# ESP32Board_Type-C.net
KiCad netlist of a schematic drawn in EAGLE
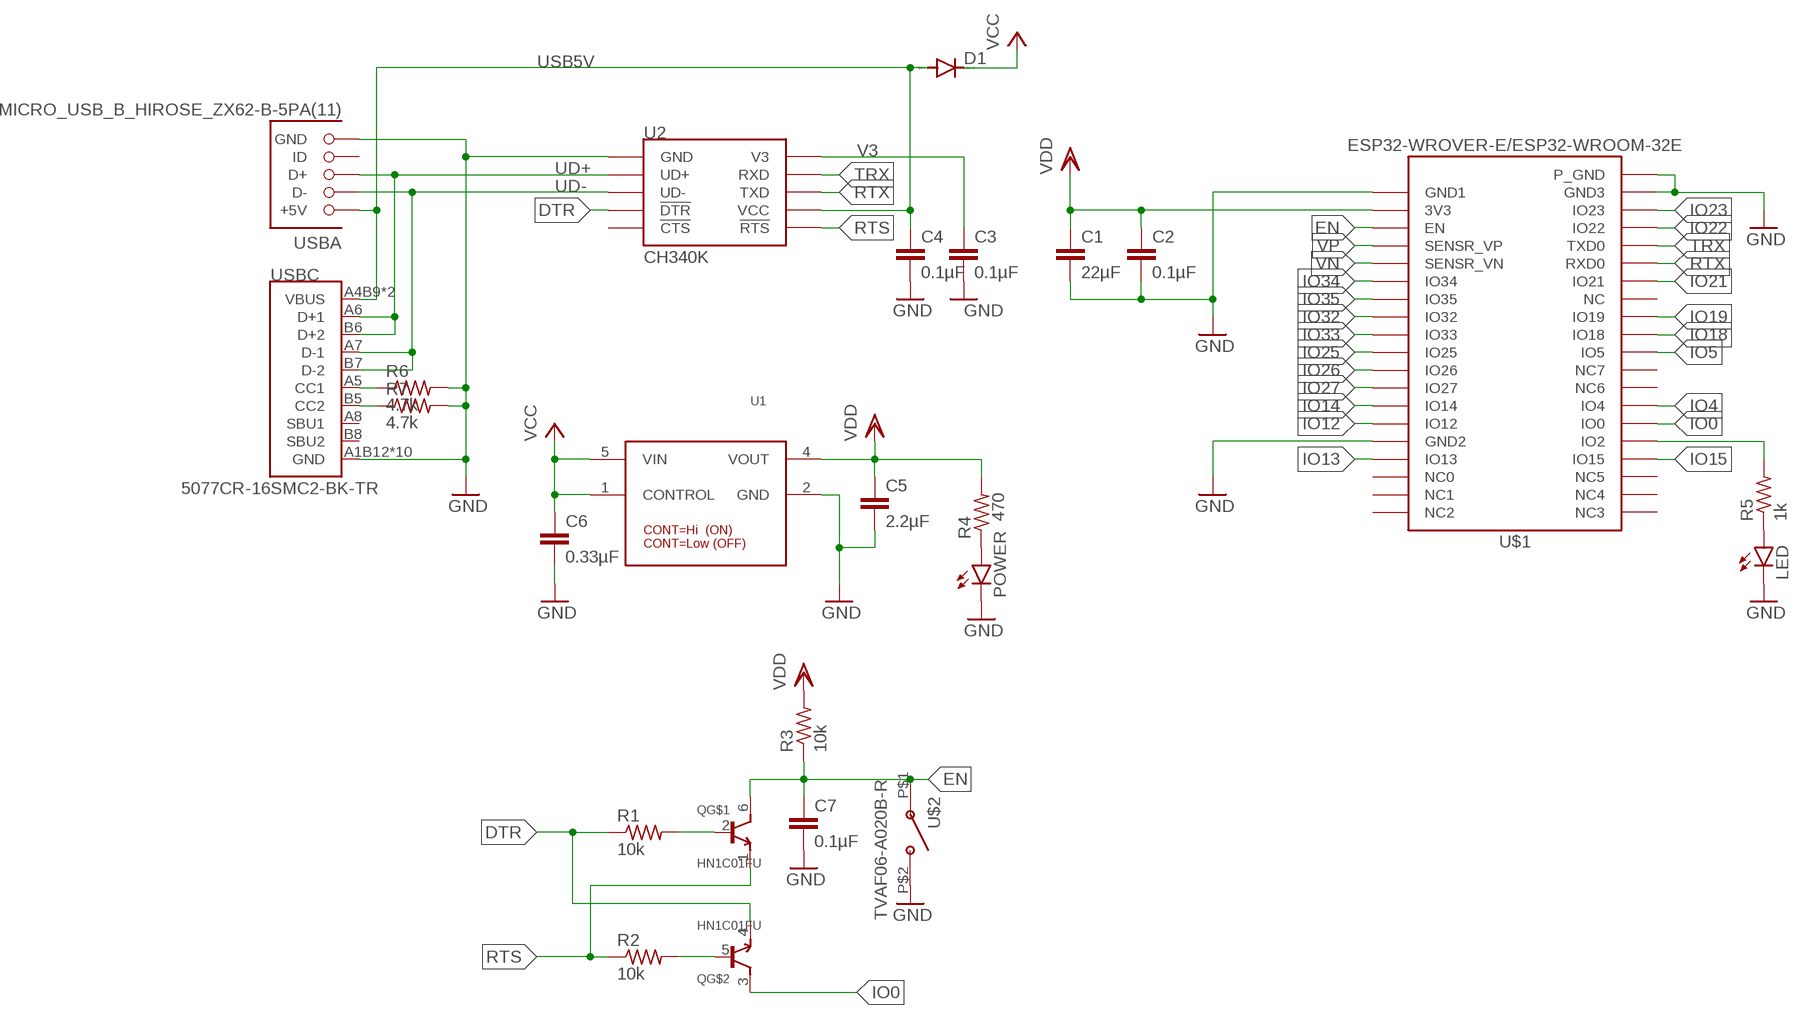
[diagram p0: schematic, sheet 1]

(export (version "E")
  (design (tool "Eeschema 10.0.6"))
  (components
    (comp (ref "C1")
      (value "22µF")
      (footprint "eagle-import:C0603K")
      (libsource (lib "eagle-import") (part "C-EUC0603K"))
    )
    (comp (ref "C2")
      (value "0.1µF")
      (footprint "eagle-import:C0603K")
      (libsource (lib "eagle-import") (part "C-EUC0603K"))
    )
    (comp (ref "C3")
      (value "0.1µF")
      (footprint "eagle-import:C0603K")
      (libsource (lib "eagle-import") (part "C-EUC0603K"))
    )
    (comp (ref "C4")
      (value "0.1µF")
      (footprint "eagle-import:C0603K")
      (libsource (lib "eagle-import") (part "C-EUC0603K"))
    )
    (comp (ref "C5")
      (value "2.2µF")
      (footprint "eagle-import:C0603K")
      (libsource (lib "eagle-import") (part "C-EUC0603K"))
    )
    (comp (ref "C6")
      (value "0.33µF")
      (footprint "eagle-import:C0603K")
      (libsource (lib "eagle-import") (part "C-EUC0603K"))
    )
    (comp (ref "C7")
      (value "0.1µF")
      (footprint "eagle-import:C0603K")
      (libsource (lib "eagle-import") (part "C-EUC0603K"))
    )
    (comp (ref "D1")
      (value "DIODE-SOD123")
      (footprint "eagle-import:SOD123")
      (libsource (lib "eagle-import") (part "DIODE-SOD123"))
    )
    (comp (ref "LED")
      (value "LEDCHIPLED_0603")
      (footprint "eagle-import:CHIPLED_0603")
      (libsource (lib "eagle-import") (part "LEDCHIPLED_0603"))
    )
    (comp (ref "POWER")
      (value "LEDCHIPLED_0603")
      (footprint "eagle-import:CHIPLED_0603")
      (libsource (lib "eagle-import") (part "LEDCHIPLED_0603"))
    )
    (comp (ref "Q")
      (value "HN1C01FU")
      (footprint "eagle-import:SOT-363")
      (libsource (lib "eagle-import") (part "HN1C01FU"))
    )
    (comp (ref "R1")
      (value "10k")
      (footprint "eagle-import:R0603")
      (libsource (lib "eagle-import") (part "R-US_R0603"))
    )
    (comp (ref "R2")
      (value "10k")
      (footprint "eagle-import:R0603")
      (libsource (lib "eagle-import") (part "R-US_R0603"))
    )
    (comp (ref "R3")
      (value "10k")
      (footprint "eagle-import:R0603")
      (libsource (lib "eagle-import") (part "R-US_R0603"))
    )
    (comp (ref "R4")
      (value "470")
      (footprint "eagle-import:R0603")
      (libsource (lib "eagle-import") (part "R-US_R0603"))
    )
    (comp (ref "R5")
      (value "1k")
      (footprint "eagle-import:R0603")
      (libsource (lib "eagle-import") (part "R-US_R0603"))
    )
    (comp (ref "R6")
      (value "4.7k")
      (footprint "eagle-import:R0603")
      (libsource (lib "eagle-import") (part "R-US_R0603"))
    )
    (comp (ref "R7")
      (value "4.7k")
      (footprint "eagle-import:R0603")
      (libsource (lib "eagle-import") (part "R-US_R0603"))
    )
    (comp (ref "U$1")
      (value "ESP32-WROVER-E/ESP32-WROOM-32E")
      (footprint "eagle-import:ESP32-WROVER-E_ESP32-WROOM-32E")
      (libsource (lib "eagle-import") (part "ESP32-WROVER-E/ESP32-WROOM-32E"))
    )
    (comp (ref "U$2")
      (value "TVAF06-A020B-R")
      (footprint "eagle-import:TVAF06-A020B-R")
      (libsource (lib "eagle-import") (part "TVAF06-A020B-R"))
    )
    (comp (ref "U1")
      (value "I-10673_NJM2884U1-33")
      (footprint "eagle-import:NJM2884U1-33")
      (libsource (lib "eagle-import") (part "I-10673_NJM2884U1-33"))
    )
    (comp (ref "U2")
      (value "CH340K")
      (footprint "eagle-import:ESSOP-10")
      (libsource (lib "eagle-import") (part "CH340K"))
    )
    (comp (ref "USBA")
      (value "MICRO_USB_B_HIROSE_ZX62-B-5PA(11)")
      (footprint "eagle-import:USB_MICRO_B-HIROSE-ZX62-B-5PA(11)")
      (libsource (lib "eagle-import") (part "MICRO_USB_B_HIROSE_ZX62-B-5PA(11)"))
    )
    (comp (ref "USBC")
      (value "5077CR-16SMC2-BK-TR")
      (footprint "eagle-import:5077CR-16SMC2-BK-TR")
      (libsource (lib "eagle-import") (part "5077CR-16SMC2-BK-TR"))
    )
  )
  (nets
    (net (code "1") (name "/UD+") (class "Default")
      (node (ref "U2") (pin "P1") (pinfunction "UD+_P1") (pintype "bidirectional"))
      (node (ref "USBA") (pin "3") (pinfunction "D+_3") (pintype "bidirectional"))
      (node (ref "USBC") (pin "A6") (pinfunction "D+1_A6") (pintype "bidirectional"))
      (node (ref "USBC") (pin "B6") (pinfunction "D+2_B6") (pintype "bidirectional"))
    )
    (net (code "2") (name "/UD-") (class "Default")
      (node (ref "U2") (pin "P2") (pinfunction "UD-_P2") (pintype "bidirectional"))
      (node (ref "USBA") (pin "2") (pinfunction "D-_2") (pintype "bidirectional"))
      (node (ref "USBC") (pin "A7") (pinfunction "D-1_A7") (pintype "bidirectional"))
      (node (ref "USBC") (pin "B7") (pinfunction "D-2_B7") (pintype "bidirectional"))
    )
    (net (code "3") (name "/USB5V") (class "Default")
      (node (ref "C4") (pin "1") (pinfunction "1_1") (pintype "passive"))
      (node (ref "D1") (pin "A") (pinfunction "A_A") (pintype "passive"))
      (node (ref "U2") (pin "P7") (pinfunction "VCC_P7") (pintype "power_in"))
      (node (ref "USBA") (pin "1") (pinfunction "+5V_1") (pintype "bidirectional"))
      (node (ref "USBC") (pin "A4B9") (pinfunction "VBUS_A4B9") (pintype "power_in"))
      (node (ref "USBC") (pin "B4A9") (pinfunction "VBUS_B4A9") (pintype "power_in"))
    )
    (net (code "4") (name "/V3") (class "Default")
      (node (ref "C3") (pin "1") (pinfunction "1_1") (pintype "passive"))
      (node (ref "U2") (pin "P10") (pinfunction "V3_P10") (pintype "power_in"))
    )
    (net (code "5") (name "DTR") (class "Default")
      (node (ref "Q") (pin "4") (pinfunction "E_4") (pintype "bidirectional"))
      (node (ref "R1") (pin "1") (pinfunction "1_1") (pintype "passive"))
      (node (ref "U2") (pin "P4") (pinfunction "~{DTR}_P4") (pintype "bidirectional"))
    )
    (net (code "6") (name "EN") (class "Default")
      (node (ref "C7") (pin "1") (pinfunction "1_1") (pintype "passive"))
      (node (ref "Q") (pin "6") (pinfunction "C_6") (pintype "bidirectional"))
      (node (ref "R3") (pin "1") (pinfunction "1_1") (pintype "passive"))
      (node (ref "U$1") (pin "EN") (pinfunction "EN_EN") (pintype "bidirectional"))
      (node (ref "U$2") (pin "P$1") (pinfunction "A_P$1") (pintype "bidirectional"))
    )
    (net (code "7") (name "GND") (class "Default")
      (node (ref "C1") (pin "2") (pinfunction "2_2") (pintype "passive"))
      (node (ref "C2") (pin "2") (pinfunction "2_2") (pintype "passive"))
      (node (ref "C3") (pin "2") (pinfunction "2_2") (pintype "passive"))
      (node (ref "C4") (pin "2") (pinfunction "2_2") (pintype "passive"))
      (node (ref "C5") (pin "2") (pinfunction "2_2") (pintype "passive"))
      (node (ref "C6") (pin "2") (pinfunction "2_2") (pintype "passive"))
      (node (ref "C7") (pin "2") (pinfunction "2_2") (pintype "passive"))
      (node (ref "LED") (pin "C") (pinfunction "C_C") (pintype "passive"))
      (node (ref "POWER") (pin "C") (pinfunction "C_C") (pintype "passive"))
      (node (ref "R6") (pin "2") (pinfunction "2_2") (pintype "passive"))
      (node (ref "R7") (pin "2") (pinfunction "2_2") (pintype "passive"))
      (node (ref "U$1") (pin "GND1") (pinfunction "GND1_GND1") (pintype "power_in"))
      (node (ref "U$1") (pin "GND2") (pinfunction "GND2_GND2") (pintype "power_in"))
      (node (ref "U$1") (pin "GND2'") (pinfunction "GND2_GND2'") (pintype "power_in"))
      (node (ref "U$1") (pin "GND3") (pinfunction "GND3_GND3") (pintype "power_in"))
      (node (ref "U$1") (pin "P_GND") (pinfunction "P_GND_P_GND") (pintype "power_in"))
      (node (ref "U$2") (pin "P$2") (pinfunction "B_P$2") (pintype "bidirectional"))
      (node (ref "U1") (pin "2") (pinfunction "GND_2") (pintype "bidirectional"))
      (node (ref "U2") (pin "P0") (pinfunction "GND_P0") (pintype "power_in"))
      (node (ref "U2") (pin "P3") (pinfunction "GND_P3") (pintype "power_in"))
      (node (ref "USBA") (pin "5") (pinfunction "GND_5") (pintype "bidirectional"))
      (node (ref "USBC") (pin "A1B12") (pinfunction "GND_A1B12") (pintype "power_in"))
      (node (ref "USBC") (pin "B1A12") (pinfunction "GND_B1A12") (pintype "power_in"))
      (node (ref "USBC") (pin "P$1") (pinfunction "GND_P$1") (pintype "power_in"))
      (node (ref "USBC") (pin "P$2") (pinfunction "GND_P$2") (pintype "power_in"))
      (node (ref "USBC") (pin "P$3") (pinfunction "GND_P$3") (pintype "power_in"))
      (node (ref "USBC") (pin "P$4") (pinfunction "GND_P$4") (pintype "power_in"))
      (node (ref "USBC") (pin "P$5") (pinfunction "GND_P$5") (pintype "power_in"))
      (node (ref "USBC") (pin "P$6") (pinfunction "GND_P$6") (pintype "power_in"))
      (node (ref "USBC") (pin "P$7") (pinfunction "GND_P$7") (pintype "power_in"))
      (node (ref "USBC") (pin "P$8") (pinfunction "GND_P$8") (pintype "power_in"))
    )
    (net (code "8") (name "IO0") (class "Default")
      (node (ref "Q") (pin "3") (pinfunction "C_3") (pintype "bidirectional"))
      (node (ref "U$1") (pin "IO0") (pinfunction "IO0_IO0") (pintype "bidirectional"))
    )
    (net (code "9") (name "IO4") (class "Default")
      (node (ref "U$1") (pin "IO4") (pinfunction "IO4_IO4") (pintype "bidirectional"))
    )
    (net (code "10") (name "IO5") (class "Default")
      (node (ref "U$1") (pin "IO5") (pinfunction "IO5_IO5") (pintype "bidirectional"))
    )
    (net (code "11") (name "IO12") (class "Default")
      (node (ref "U$1") (pin "IO12") (pinfunction "IO12_IO12") (pintype "bidirectional"))
    )
    (net (code "12") (name "IO13") (class "Default")
      (node (ref "U$1") (pin "IO13") (pinfunction "IO13_IO13") (pintype "bidirectional"))
      (node (ref "U$1") (pin "IO13'") (pinfunction "IO13_IO13'") (pintype "bidirectional"))
    )
    (net (code "13") (name "IO14") (class "Default")
      (node (ref "U$1") (pin "IO14") (pinfunction "IO14_IO14") (pintype "bidirectional"))
    )
    (net (code "14") (name "IO15") (class "Default")
      (node (ref "U$1") (pin "IO15") (pinfunction "IO15_IO15") (pintype "bidirectional"))
      (node (ref "U$1") (pin "IO15'") (pinfunction "IO15_IO15'") (pintype "bidirectional"))
    )
    (net (code "15") (name "IO18") (class "Default")
      (node (ref "U$1") (pin "IO18") (pinfunction "IO18_IO18") (pintype "bidirectional"))
    )
    (net (code "16") (name "IO19") (class "Default")
      (node (ref "U$1") (pin "IO19") (pinfunction "IO19_IO19") (pintype "bidirectional"))
    )
    (net (code "17") (name "IO21") (class "Default")
      (node (ref "U$1") (pin "IO21") (pinfunction "IO21_IO21") (pintype "bidirectional"))
    )
    (net (code "18") (name "IO22") (class "Default")
      (node (ref "U$1") (pin "IO22") (pinfunction "IO22_IO22") (pintype "bidirectional"))
    )
    (net (code "19") (name "IO23") (class "Default")
      (node (ref "U$1") (pin "IO23") (pinfunction "IO23_IO23") (pintype "bidirectional"))
    )
    (net (code "20") (name "IO25") (class "Default")
      (node (ref "U$1") (pin "IO25") (pinfunction "IO25_IO25") (pintype "bidirectional"))
    )
    (net (code "21") (name "IO26") (class "Default")
      (node (ref "U$1") (pin "IO26") (pinfunction "IO26_IO26") (pintype "bidirectional"))
    )
    (net (code "22") (name "IO27") (class "Default")
      (node (ref "U$1") (pin "IO27") (pinfunction "IO27_IO27") (pintype "bidirectional"))
    )
    (net (code "23") (name "IO32") (class "Default")
      (node (ref "U$1") (pin "IO32") (pinfunction "IO32_IO32") (pintype "bidirectional"))
    )
    (net (code "24") (name "IO33") (class "Default")
      (node (ref "U$1") (pin "IO33") (pinfunction "IO33_IO33") (pintype "bidirectional"))
    )
    (net (code "25") (name "IO34") (class "Default")
      (node (ref "U$1") (pin "IO34") (pinfunction "IO34_IO34") (pintype "bidirectional"))
    )
    (net (code "26") (name "IO35") (class "Default")
      (node (ref "U$1") (pin "IO35") (pinfunction "IO35_IO35") (pintype "bidirectional"))
    )
    (net (code "27") (name "Net-(LED-PadA)") (class "Default")
      (node (ref "LED") (pin "A") (pinfunction "A_A") (pintype "passive"))
      (node (ref "R5") (pin "1") (pinfunction "1_1") (pintype "passive"))
    )
    (net (code "28") (name "Net-(POWER-PadA)") (class "Default")
      (node (ref "POWER") (pin "A") (pinfunction "A_A") (pintype "passive"))
      (node (ref "R4") (pin "1") (pinfunction "1_1") (pintype "passive"))
    )
    (net (code "29") (name "Net-(QA-B)") (class "Default")
      (node (ref "Q") (pin "2") (pinfunction "B_2") (pintype "bidirectional"))
      (node (ref "R1") (pin "2") (pinfunction "2_2") (pintype "passive"))
    )
    (net (code "30") (name "Net-(QB-B)") (class "Default")
      (node (ref "Q") (pin "5") (pinfunction "B_5") (pintype "bidirectional"))
      (node (ref "R2") (pin "2") (pinfunction "2_2") (pintype "passive"))
    )
    (net (code "31") (name "Net-(R5-Pad2)") (class "Default")
      (node (ref "R5") (pin "2") (pinfunction "2_2") (pintype "passive"))
      (node (ref "U$1") (pin "IO2") (pinfunction "IO2_IO2") (pintype "bidirectional"))
      (node (ref "U$1") (pin "IO2'") (pinfunction "IO2_IO2'") (pintype "bidirectional"))
    )
    (net (code "32") (name "Net-(USBC-CC1)") (class "Default")
      (node (ref "R6") (pin "1") (pinfunction "1_1") (pintype "passive"))
      (node (ref "USBC") (pin "A5") (pinfunction "CC1_A5") (pintype "bidirectional"))
    )
    (net (code "33") (name "Net-(USBC-CC2)") (class "Default")
      (node (ref "R7") (pin "1") (pinfunction "1_1") (pintype "passive"))
      (node (ref "USBC") (pin "B5") (pinfunction "CC2_B5") (pintype "bidirectional"))
    )
    (net (code "34") (name "RTS") (class "Default")
      (node (ref "Q") (pin "1") (pinfunction "E_1") (pintype "bidirectional"))
      (node (ref "R2") (pin "1") (pinfunction "1_1") (pintype "passive"))
      (node (ref "U2") (pin "P6") (pinfunction "~{RTS}_P6") (pintype "bidirectional"))
    )
    (net (code "35") (name "RTX") (class "Default")
      (node (ref "U$1") (pin "RXD0") (pinfunction "RXD0_RXD0") (pintype "bidirectional"))
      (node (ref "U2") (pin "P8") (pinfunction "TXD_P8") (pintype "bidirectional"))
    )
    (net (code "36") (name "TRX") (class "Default")
      (node (ref "U$1") (pin "TXD0") (pinfunction "TXD0_TXD0") (pintype "bidirectional"))
      (node (ref "U2") (pin "P9") (pinfunction "RXD_P9") (pintype "bidirectional"))
    )
    (net (code "37") (name "VCC") (class "Default")
      (node (ref "C6") (pin "1") (pinfunction "1_1") (pintype "passive"))
      (node (ref "D1") (pin "C") (pinfunction "C_C") (pintype "passive"))
      (node (ref "U1") (pin "1") (pinfunction "CONTROL_1") (pintype "bidirectional"))
      (node (ref "U1") (pin "5") (pinfunction "VIN_5") (pintype "bidirectional"))
    )
    (net (code "38") (name "VDD") (class "Default")
      (node (ref "C1") (pin "1") (pinfunction "1_1") (pintype "passive"))
      (node (ref "C2") (pin "1") (pinfunction "1_1") (pintype "passive"))
      (node (ref "C5") (pin "1") (pinfunction "1_1") (pintype "passive"))
      (node (ref "R3") (pin "2") (pinfunction "2_2") (pintype "passive"))
      (node (ref "R4") (pin "2") (pinfunction "2_2") (pintype "passive"))
      (node (ref "U$1") (pin "3V3") (pinfunction "3V3_3V3") (pintype "power_in"))
      (node (ref "U1") (pin "4") (pinfunction "VOUT_4") (pintype "bidirectional"))
    )
    (net (code "39") (name "VN") (class "Default")
      (node (ref "U$1") (pin "SENSOR_VN") (pinfunction "SENSR_VN_SENSOR_VN") (pintype "bidirectional"))
    )
    (net (code "40") (name "VP") (class "Default")
      (node (ref "U$1") (pin "SENSOR_VP") (pinfunction "SENSR_VP_SENSOR_VP") (pintype "bidirectional"))
    )
    (net (code "41") (name "unconnected-(U$1-NC0-PadNC0')") (class "Default")
      (node (ref "U$1") (pin "NC0'") (pinfunction "NC0_NC0'") (pintype "no_connect"))
    )
    (net (code "42") (name "unconnected-(U$1-NC1-PadNC1')") (class "Default")
      (node (ref "U$1") (pin "NC1'") (pinfunction "NC1_NC1'") (pintype "no_connect"))
    )
    (net (code "43") (name "unconnected-(U$1-NC2-PadNC2')") (class "Default")
      (node (ref "U$1") (pin "NC2'") (pinfunction "NC2_NC2'") (pintype "no_connect"))
    )
    (net (code "44") (name "unconnected-(U$1-NC3-PadNC3')") (class "Default")
      (node (ref "U$1") (pin "NC3'") (pinfunction "NC3_NC3'") (pintype "no_connect"))
    )
    (net (code "45") (name "unconnected-(U$1-NC4-PadNC4')") (class "Default")
      (node (ref "U$1") (pin "NC4'") (pinfunction "NC4_NC4'") (pintype "no_connect"))
    )
    (net (code "46") (name "unconnected-(U$1-NC5-PadNC5')") (class "Default")
      (node (ref "U$1") (pin "NC5'") (pinfunction "NC5_NC5'") (pintype "no_connect"))
    )
    (net (code "47") (name "unconnected-(U$1-NC6-PadIO16)") (class "Default")
      (node (ref "U$1") (pin "IO16") (pinfunction "NC6_IO16") (pintype "no_connect"))
    )
    (net (code "48") (name "unconnected-(U$1-NC7-PadIO17)") (class "Default")
      (node (ref "U$1") (pin "IO17") (pinfunction "NC7_IO17") (pintype "no_connect"))
    )
    (net (code "49") (name "unconnected-(U$1-PadNC)") (class "Default")
      (node (ref "U$1") (pin "NC") (pinfunction "NC_NC") (pintype "no_connect"))
    )
    (net (code "50") (name "unconnected-(U$1-PadNC0)") (class "Default")
      (node (ref "U$1") (pin "NC0") (pinfunction "NC0_NC0") (pintype "no_connect"))
    )
    (net (code "51") (name "unconnected-(U$1-PadNC1)") (class "Default")
      (node (ref "U$1") (pin "NC1") (pinfunction "NC1_NC1") (pintype "no_connect"))
    )
    (net (code "52") (name "unconnected-(U$1-PadNC2)") (class "Default")
      (node (ref "U$1") (pin "NC2") (pinfunction "NC2_NC2") (pintype "no_connect"))
    )
    (net (code "53") (name "unconnected-(U$1-PadNC3)") (class "Default")
      (node (ref "U$1") (pin "NC3") (pinfunction "NC3_NC3") (pintype "no_connect"))
    )
    (net (code "54") (name "unconnected-(U$1-PadNC4)") (class "Default")
      (node (ref "U$1") (pin "NC4") (pinfunction "NC4_NC4") (pintype "no_connect"))
    )
    (net (code "55") (name "unconnected-(U$1-PadNC5)") (class "Default")
      (node (ref "U$1") (pin "NC5") (pinfunction "NC5_NC5") (pintype "no_connect"))
    )
    (net (code "56") (name "unconnected-(U2-~{CTS}-PadP5)") (class "Default")
      (node (ref "U2") (pin "P5") (pinfunction "~{CTS}_P5") (pintype "bidirectional"))
    )
    (net (code "57") (name "unconnected-(USBA-ID-Pad4)") (class "Default")
      (node (ref "USBA") (pin "4") (pinfunction "ID_4") (pintype "bidirectional"))
    )
    (net (code "58") (name "unconnected-(USBC-SBU1-PadA8)") (class "Default")
      (node (ref "USBC") (pin "A8") (pinfunction "SBU1_A8") (pintype "bidirectional"))
    )
    (net (code "59") (name "unconnected-(USBC-SBU2-PadB8)") (class "Default")
      (node (ref "USBC") (pin "B8") (pinfunction "SBU2_B8") (pintype "bidirectional"))
    )
  )
)
